# VG.net
KiCad netlist of a schematic drawn in Altium Designer
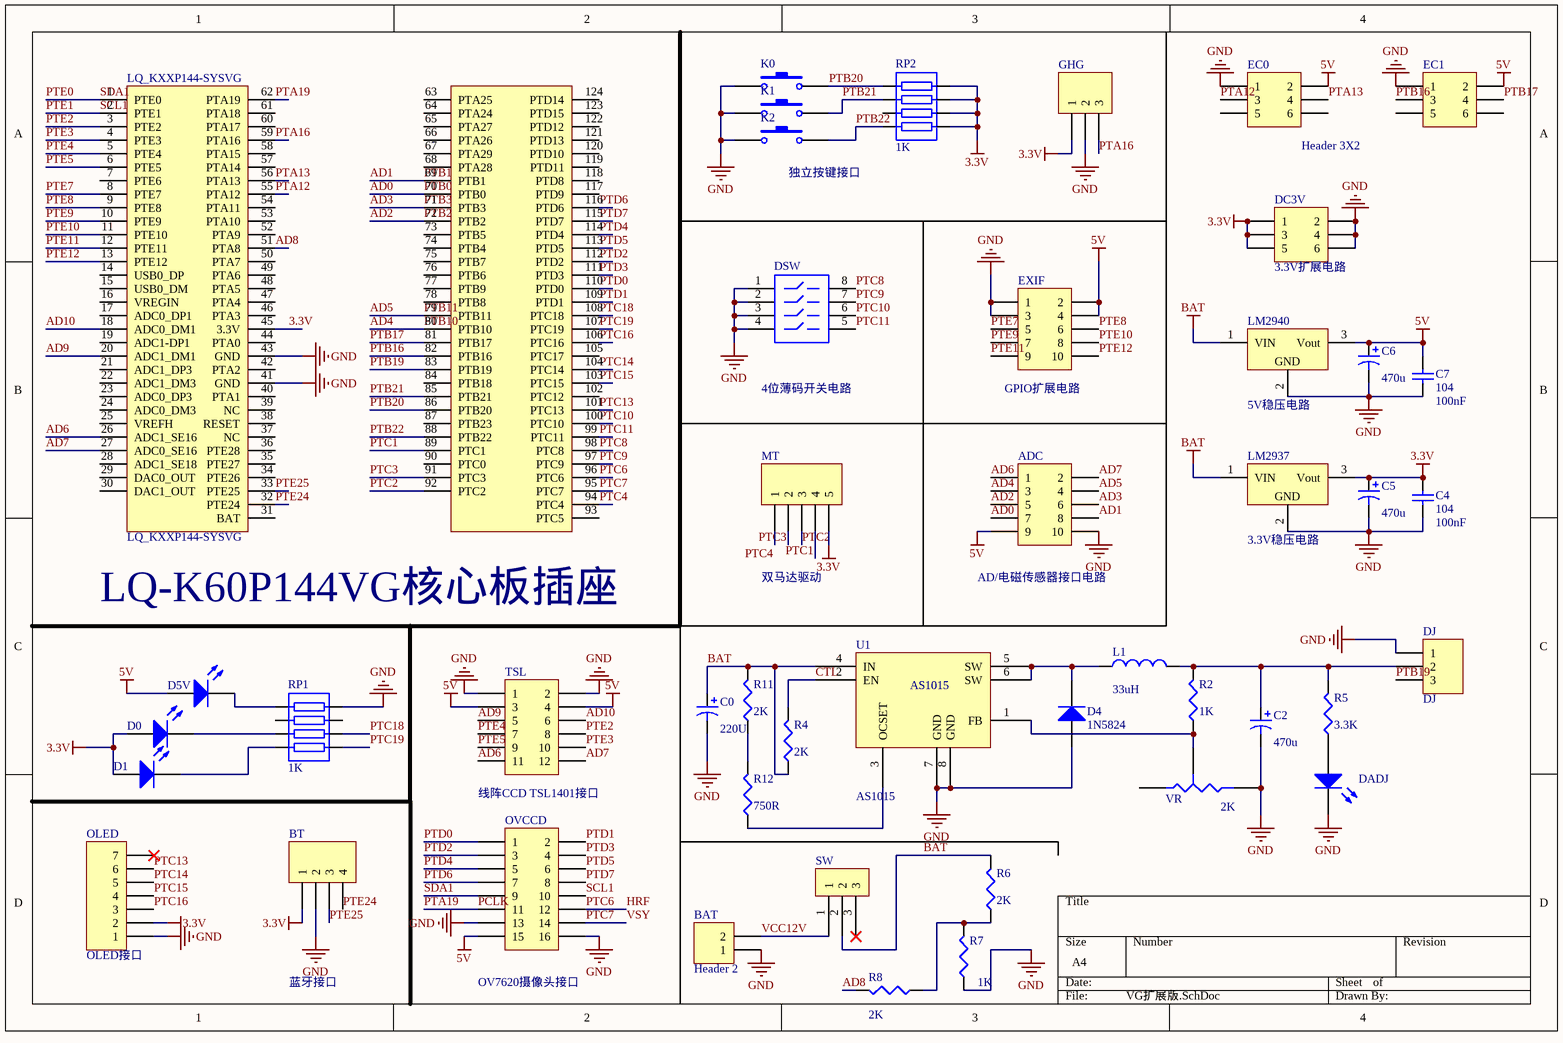
[diagram p0: VG扩展版.SchDoc]

(export (version "E")
  (design (tool "Eeschema 10.0.6"))
  (components
    (comp (ref "ADC")
      (value "AD/电磁传感器接口电路")
      (footprint "HDR2X5")
      (description "Header, 5-Pin, Dual row")
      (fields (field (name "PUBLISHER") "Altium Limited"))
      (libsource (lib "VG扩展板") (part "Header 5X2"))
    )
    (comp (ref "BAT")
      (value "Header 2")
      (footprint "power1")
      (description "Header, 2-Pin")
      (fields (field (name "PUBLISHER") "Altium Limited"))
      (libsource (lib "VG扩展板") (part "Header 2"))
    )
    (comp (ref "BT")
      (value "蓝牙接口")
      (footprint "HDR1X4")
      (description "Header, 4-Pin")
      (fields (field (name "PUBLISHER") "Altium Limited"))
      (libsource (lib "VG扩展板") (part "Header 4"))
    )
    (comp (ref "C0")
      (value "220U")
      (footprint "rb -5")
      (description "Polarized Capacitor (Radial)")
      (fields (field (name "PUBLISHER") "Altium Limited"))
      (libsource (lib "VG扩展板") (part "Cap Pol1"))
    )
    (comp (ref "C2")
      (value "470u")
      (footprint "3527")
      (description "Polarized Capacitor (Surface Mount)")
      (fields (field (name "PUBLISHER") "Altium Limited"))
      (libsource (lib "VG扩展板") (part "Cap Pol3"))
    )
    (comp (ref "C4")
      (value "104")
      (footprint "0603")
      (description "Capacitor (Semiconductor SIM Model)")
      (fields (field (name "ALTIUM_VALUE") "100nF") (field (name "PUBLISHER") "Altium Limited"))
      (libsource (lib "VG扩展板") (part "Cap Semi"))
    )
    (comp (ref "C5")
      (value "470u")
      (footprint "3527")
      (description "Polarized Capacitor (Surface Mount)")
      (fields (field (name "PUBLISHER") "Altium Limited"))
      (libsource (lib "VG扩展板") (part "Cap Pol3"))
    )
    (comp (ref "C6")
      (value "470u")
      (footprint "3527")
      (description "Polarized Capacitor (Surface Mount)")
      (fields (field (name "PUBLISHER") "Altium Limited"))
      (libsource (lib "VG扩展板") (part "Cap Pol3"))
    )
    (comp (ref "C7")
      (value "104")
      (footprint "0603")
      (description "Capacitor (Semiconductor SIM Model)")
      (fields (field (name "ALTIUM_VALUE") "100nF") (field (name "PUBLISHER") "Altium Limited"))
      (libsource (lib "VG扩展板") (part "Cap Semi"))
    )
    (comp (ref "D0")
      (value "~")
      (footprint "3.2X1.6X1.1")
      (description "Typical BLUE SiC LED")
      (fields (field (name "PUBLISHER") "Altium Limited"))
      (libsource (lib "VG扩展板") (part "LED3"))
    )
    (comp (ref "D1")
      (value "~")
      (footprint "3.2X1.6X1.1")
      (description "Typical BLUE SiC LED")
      (fields (field (name "PUBLISHER") "Altium Limited"))
      (libsource (lib "VG扩展板") (part "LED3"))
    )
    (comp (ref "D4")
      (value "1N5824")
      (footprint "1812_DIODE")
      (description "Default Diode")
      (fields (field (name "PUBLISHER") "Altium Limited"))
      (libsource (lib "VG扩展板") (part "Diode"))
    )
    (comp (ref "D5V")
      (value "~")
      (footprint "3.2X1.6X1.1")
      (description "Typical BLUE SiC LED")
      (fields (field (name "PUBLISHER") "Altium Limited"))
      (libsource (lib "VG扩展板") (part "LED3"))
    )
    (comp (ref "DADJ")
      (value "~")
      (footprint "3.2X1.6X1.1")
      (description "Typical BLUE SiC LED")
      (fields (field (name "PUBLISHER") "Altium Limited"))
      (libsource (lib "VG扩展板") (part "LED3"))
    )
    (comp (ref "DC3V")
      (value "3.3V扩展电路")
      (footprint "HDR2X3")
      (description "Header, 3-Pin, Dual row, Right Angle")
      (fields (field (name "PUBLISHER") "Altium Limited"))
      (libsource (lib "VG扩展板") (part "Header 3X2H"))
    )
    (comp (ref "DJ")
      (value "DJ")
      (footprint "HDR1X3")
      (description "Header, 3-Pin")
      (fields (field (name "PUBLISHER") "Altium Limited"))
      (libsource (lib "VG扩展板") (part "Header 3"))
    )
    (comp (ref "DSW")
      (value "4位薄码开关电路")
      (footprint "DIP-8")
      (description "DIP Switch")
      (fields (field (name "PUBLISHER") "Altium Limited"))
      (libsource (lib "VG扩展板") (part "SW-DIP4"))
    )
    (comp (ref "EC0")
      (value "~")
      (footprint "HDR2X3")
      (description "Header, 3-Pin, Dual row")
      (fields (field (name "PUBLISHER") "Altium Limited"))
      (libsource (lib "VG扩展板") (part "Header 3X2"))
    )
    (comp (ref "EC1")
      (value "Header 3X2")
      (footprint "HDR2X3")
      (description "Header, 3-Pin, Dual row")
      (fields (field (name "PUBLISHER") "Altium Limited"))
      (libsource (lib "VG扩展板") (part "Header 3X2"))
    )
    (comp (ref "EXIF")
      (value "GPIO扩展电路")
      (footprint "HDR2X5")
      (description "Header, 5-Pin, Dual row")
      (fields (field (name "PUBLISHER") "Altium Limited"))
      (libsource (lib "VG扩展板") (part "Header 5X2"))
    )
    (comp (ref "GHG")
      (value "~")
      (footprint "HDR1X3")
      (description "Header, 3-Pin")
      (fields (field (name "PUBLISHER") "Altium Limited"))
      (libsource (lib "") (part "Header 3_1"))
    )
    (comp (ref "K0")
      (value "~")
      (footprint "2512R")
      (description "Switch")
      (fields (field (name "PUBLISHER") "Altium Limited"))
      (libsource (lib "VG扩展板") (part "SW-PB"))
    )
    (comp (ref "K1")
      (value "~")
      (footprint "2512R")
      (description "Switch")
      (fields (field (name "PUBLISHER") "Altium Limited"))
      (libsource (lib "VG扩展板") (part "SW-PB"))
    )
    (comp (ref "K2")
      (value "~")
      (footprint "2512R")
      (description "Switch")
      (fields (field (name "PUBLISHER") "Altium Limited"))
      (libsource (lib "VG扩展板") (part "SW-PB"))
    )
    (comp (ref "L1")
      (value "33uH")
      (footprint "CL1010")
      (description "Inductor")
      (fields (field (name "PUBLISHER") "Altium Limited"))
      (libsource (lib "VG扩展板") (part "Inductor"))
    )
    (comp (ref "LM2937")
      (value "3.3V稳压电路")
      (footprint "TO263-3")
      (description "固定5V输出直流稳压芯片")
      (libsource (lib "VG扩展板") (part "LM2940"))
    )
    (comp (ref "LM2940")
      (value "5V稳压电路")
      (footprint "TO263-3")
      (description "固定5V输出直流稳压芯片")
      (libsource (lib "VG扩展板") (part "LM2940"))
    )
    (comp (ref "LQ_KXXP144-SYSVG")
      (value "LQ_KXXP144-SYSVG")
      (footprint "LQ_KXXP144-SYSVG")
      (libsource (lib "VG扩展板") (part "LQ_KXXP144-SYSVG"))
    )
    (comp (ref "MT")
      (value "双马达驱动")
      (footprint "HDR1X5")
      (description "Header, 5-Pin")
      (fields (field (name "PUBLISHER") "Altium Limited"))
      (libsource (lib "VG扩展板") (part "Header 5"))
    )
    (comp (ref "OLED")
      (value "OLED接口")
      (footprint "HDR1X7")
      (description "Header, 7-Pin")
      (fields (field (name "PUBLISHER") "Altium Limited"))
      (libsource (lib "VG扩展板") (part "Header 7"))
    )
    (comp (ref "OVCCD")
      (value "OV7620摄像头接口")
      (footprint "HDR2X8")
      (description "Header, 8-Pin, Dual row")
      (fields (field (name "PUBLISHER") "Altium Limited"))
      (libsource (lib "VG扩展板") (part "Header 8X2"))
    )
    (comp (ref "R2")
      (value "1K")
      (footprint "J1-0603")
      (description "Resistor")
      (fields (field (name "PUBLISHER") "Altium Limited"))
      (libsource (lib "VG扩展板") (part "Res3"))
    )
    (comp (ref "R4")
      (value "2K")
      (footprint "J1-0603")
      (description "Resistor")
      (fields (field (name "PUBLISHER") "Altium Limited"))
      (libsource (lib "VG扩展板") (part "Res3"))
    )
    (comp (ref "R5")
      (value "3.3K")
      (footprint "J1-0603")
      (description "Resistor")
      (fields (field (name "PUBLISHER") "Altium Limited"))
      (libsource (lib "VG扩展板") (part "Res3"))
    )
    (comp (ref "R6")
      (value "2K")
      (footprint "J1-0603")
      (description "Resistor")
      (fields (field (name "PUBLISHER") "Altium Limited"))
      (libsource (lib "VG扩展板") (part "Res3"))
    )
    (comp (ref "R7")
      (value "1K")
      (footprint "J1-0603")
      (description "Resistor")
      (fields (field (name "PUBLISHER") "Altium Limited"))
      (libsource (lib "VG扩展板") (part "Res3"))
    )
    (comp (ref "R8")
      (value "2K")
      (footprint "J1-0603")
      (description "Resistor")
      (fields (field (name "PUBLISHER") "Altium Limited"))
      (libsource (lib "VG扩展板") (part "Res3"))
    )
    (comp (ref "R11")
      (value "2K")
      (footprint "J1-0603")
      (description "Resistor")
      (fields (field (name "PUBLISHER") "Altium Limited"))
      (libsource (lib "VG扩展板") (part "Res3"))
    )
    (comp (ref "R12")
      (value "750R")
      (footprint "J1-0603")
      (description "Resistor")
      (fields (field (name "PUBLISHER") "Altium Limited"))
      (libsource (lib "VG扩展板") (part "Res3"))
    )
    (comp (ref "RP1") (value "1K") (footprint "RESPACK4_SMD") (libsource (lib "VG扩展板") (part "RESPACK4")))
    (comp (ref "RP2") (value "1K") (footprint "RESPACK4_SMD") (libsource (lib "VG扩展板") (part "RESPACK4")))
    (comp (ref "SW") (value "~") (footprint "钮子开关 - duplicate") (libsource (lib "VG扩展板") (part "钮子开关")))
    (comp (ref "TSL")
      (value "线阵CCD TSL1401接口")
      (footprint "HDR2X6")
      (description "Header, 6-Pin, Dual row")
      (fields (field (name "PUBLISHER") "Altium Limited"))
      (libsource (lib "VG扩展板") (part "Header 6X2"))
    )
    (comp (ref "U1") (value "AS1015") (footprint "SOP8L") (libsource (lib "VG扩展板") (part "AS1015")))
    (comp (ref "VR")
      (value "2K")
      (footprint "3362")
      (description "Tapped Resistor")
      (fields (field (name "PUBLISHER") "Altium Limited"))
      (libsource (lib "VG扩展板") (part "Res Tap"))
    )
  )
  (nets
    (net (code "1") (name "/AD0") (class "Default")
      (node (ref "ADC") (pin "7") (pinfunction "7_7") (pintype "passive"))
      (node (ref "LQ_KXXP144-SYSVG") (pin "70") (pinfunction "PTB0_70") (pintype "passive"))
    )
    (net (code "2") (name "/AD1") (class "Default")
      (node (ref "ADC") (pin "8") (pinfunction "8_8") (pintype "passive"))
      (node (ref "LQ_KXXP144-SYSVG") (pin "69") (pinfunction "PTB1_69") (pintype "passive"))
    )
    (net (code "3") (name "/AD2") (class "Default")
      (node (ref "ADC") (pin "5") (pinfunction "5_5") (pintype "passive"))
      (node (ref "LQ_KXXP144-SYSVG") (pin "72") (pinfunction "PTB2_72") (pintype "passive"))
    )
    (net (code "4") (name "/AD3") (class "Default")
      (node (ref "ADC") (pin "6") (pinfunction "6_6") (pintype "passive"))
      (node (ref "LQ_KXXP144-SYSVG") (pin "71") (pinfunction "PTB3_71") (pintype "passive"))
    )
    (net (code "5") (name "/AD4") (class "Default")
      (node (ref "ADC") (pin "3") (pinfunction "3_3") (pintype "passive"))
      (node (ref "LQ_KXXP144-SYSVG") (pin "80") (pinfunction "PTB10_80") (pintype "passive"))
    )
    (net (code "6") (name "/AD5") (class "Default")
      (node (ref "ADC") (pin "4") (pinfunction "4_4") (pintype "passive"))
      (node (ref "LQ_KXXP144-SYSVG") (pin "79") (pinfunction "PTB11_79") (pintype "passive"))
    )
    (net (code "7") (name "/AD6") (class "Default")
      (node (ref "ADC") (pin "1") (pinfunction "1_1") (pintype "passive"))
      (node (ref "LQ_KXXP144-SYSVG") (pin "26") (pinfunction "ADC1_SE16_26") (pintype "passive"))
      (node (ref "TSL") (pin "11") (pinfunction "11_11") (pintype "passive"))
    )
    (net (code "8") (name "/AD7") (class "Default")
      (node (ref "ADC") (pin "2") (pinfunction "2_2") (pintype "passive"))
      (node (ref "LQ_KXXP144-SYSVG") (pin "27") (pinfunction "ADC0_SE16_27") (pintype "passive"))
      (node (ref "TSL") (pin "12") (pinfunction "12_12") (pintype "passive"))
    )
    (net (code "9") (name "/AD8") (class "Default")
      (node (ref "LQ_KXXP144-SYSVG") (pin "51") (pinfunction "PTA8_51") (pintype "passive"))
      (node (ref "R8") (pin "2") (pinfunction "2_2") (pintype "passive"))
    )
    (net (code "10") (name "/AD9") (class "Default")
      (node (ref "LQ_KXXP144-SYSVG") (pin "20") (pinfunction "ADC1_DM1_20") (pintype "passive"))
      (node (ref "TSL") (pin "5") (pinfunction "5_5") (pintype "passive"))
    )
    (net (code "11") (name "/AD10") (class "Default")
      (node (ref "LQ_KXXP144-SYSVG") (pin "18") (pinfunction "ADC0_DM1_18") (pintype "passive"))
      (node (ref "TSL") (pin "6") (pinfunction "6_6") (pintype "passive"))
    )
    (net (code "12") (name "/CTL") (class "Default")
      (node (ref "R4") (pin "2") (pinfunction "2_2") (pintype "passive"))
      (node (ref "U1") (pin "2") (pinfunction "EN_2") (pintype "passive"))
    )
    (net (code "13") (name "/HRF") (class "Default")
      (node (ref "LQ_KXXP144-SYSVG") (pin "96") (pinfunction "PTC6_96") (pintype "passive"))
      (node (ref "OVCCD") (pin "12") (pinfunction "12_12") (pintype "passive"))
    )
    (net (code "14") (name "/PCLK") (class "Default")
      (node (ref "LQ_KXXP144-SYSVG") (pin "62") (pinfunction "PTA19_62") (pintype "passive"))
      (node (ref "OVCCD") (pin "11") (pinfunction "11_11") (pintype "passive"))
    )
    (net (code "15") (name "/PTA12") (class "Default")
      (node (ref "EC0") (pin "3") (pinfunction "3_3") (pintype "passive"))
      (node (ref "LQ_KXXP144-SYSVG") (pin "55") (pinfunction "PTA12_55") (pintype "passive"))
    )
    (net (code "16") (name "/PTA13") (class "Default")
      (node (ref "EC0") (pin "4") (pinfunction "4_4") (pintype "passive"))
      (node (ref "LQ_KXXP144-SYSVG") (pin "56") (pinfunction "PTA13_56") (pintype "passive"))
    )
    (net (code "17") (name "/PTA16") (class "Default")
      (node (ref "GHG") (pin "3") (pinfunction "3_3") (pintype "passive"))
      (node (ref "LQ_KXXP144-SYSVG") (pin "59") (pinfunction "PTA16_59") (pintype "passive"))
    )
    (net (code "18") (name "/PTB16") (class "Default")
      (node (ref "EC1") (pin "3") (pinfunction "3_3") (pintype "passive"))
      (node (ref "LQ_KXXP144-SYSVG") (pin "82") (pinfunction "PTB16_82") (pintype "passive"))
    )
    (net (code "19") (name "/PTB17") (class "Default")
      (node (ref "EC1") (pin "4") (pinfunction "4_4") (pintype "passive"))
      (node (ref "LQ_KXXP144-SYSVG") (pin "81") (pinfunction "PTB17_81") (pintype "passive"))
    )
    (net (code "20") (name "/PTB19") (class "Default")
      (node (ref "DJ") (pin "3") (pinfunction "3_3") (pintype "passive"))
      (node (ref "LQ_KXXP144-SYSVG") (pin "83") (pinfunction "PTB19_83") (pintype "passive"))
    )
    (net (code "21") (name "/PTB20") (class "Default")
      (node (ref "K0") (pin "2") (pinfunction "2_2") (pintype "passive"))
      (node (ref "LQ_KXXP144-SYSVG") (pin "86") (pinfunction "PTB20_86") (pintype "passive"))
      (node (ref "RP2") (pin "1") (pinfunction "1_1") (pintype "passive"))
    )
    (net (code "22") (name "/PTB21") (class "Default")
      (node (ref "K1") (pin "2") (pinfunction "2_2") (pintype "passive"))
      (node (ref "LQ_KXXP144-SYSVG") (pin "85") (pinfunction "PTB21_85") (pintype "passive"))
      (node (ref "RP2") (pin "3") (pinfunction "3_3") (pintype "passive"))
    )
    (net (code "23") (name "/PTB22") (class "Default")
      (node (ref "K2") (pin "2") (pinfunction "2_2") (pintype "passive"))
      (node (ref "LQ_KXXP144-SYSVG") (pin "88") (pinfunction "PTB22_88") (pintype "passive"))
      (node (ref "RP2") (pin "7") (pinfunction "7_7") (pintype "passive"))
    )
    (net (code "24") (name "/PTC1") (class "Default")
      (node (ref "LQ_KXXP144-SYSVG") (pin "89") (pinfunction "PTC1_89") (pintype "passive"))
      (node (ref "MT") (pin "4") (pinfunction "4_4") (pintype "passive"))
    )
    (net (code "25") (name "/PTC2") (class "Default")
      (node (ref "LQ_KXXP144-SYSVG") (pin "92") (pinfunction "PTC2_92") (pintype "passive"))
      (node (ref "MT") (pin "3") (pinfunction "3_3") (pintype "passive"))
    )
    (net (code "26") (name "/PTC3") (class "Default")
      (node (ref "LQ_KXXP144-SYSVG") (pin "91") (pinfunction "PTC3_91") (pintype "passive"))
      (node (ref "MT") (pin "2") (pinfunction "2_2") (pintype "passive"))
    )
    (net (code "27") (name "/PTC4") (class "Default")
      (node (ref "LQ_KXXP144-SYSVG") (pin "94") (pinfunction "PTC4_94") (pintype "passive"))
      (node (ref "MT") (pin "1") (pinfunction "1_1") (pintype "passive"))
    )
    (net (code "28") (name "/PTC7") (class "Default")
      (node (ref "LQ_KXXP144-SYSVG") (pin "95") (pinfunction "PTC7_95") (pintype "passive"))
      (node (ref "OVCCD") (pin "14") (pinfunction "14_14") (pintype "passive"))
    )
    (net (code "29") (name "/PTC8") (class "Default")
      (node (ref "DSW") (pin "8") (pinfunction "8_8") (pintype "passive"))
      (node (ref "LQ_KXXP144-SYSVG") (pin "98") (pinfunction "PTC8_98") (pintype "passive"))
    )
    (net (code "30") (name "/PTC9") (class "Default")
      (node (ref "DSW") (pin "7") (pinfunction "7_7") (pintype "passive"))
      (node (ref "LQ_KXXP144-SYSVG") (pin "97") (pinfunction "PTC9_97") (pintype "passive"))
    )
    (net (code "31") (name "/PTC10") (class "Default")
      (node (ref "DSW") (pin "6") (pinfunction "6_6") (pintype "passive"))
      (node (ref "LQ_KXXP144-SYSVG") (pin "100") (pinfunction "PTC10_100") (pintype "passive"))
    )
    (net (code "32") (name "/PTC11") (class "Default")
      (node (ref "DSW") (pin "5") (pinfunction "5_5") (pintype "passive"))
      (node (ref "LQ_KXXP144-SYSVG") (pin "99") (pinfunction "PTC11_99") (pintype "passive"))
    )
    (net (code "33") (name "/PTC13") (class "Default")
      (node (ref "LQ_KXXP144-SYSVG") (pin "101") (pinfunction "PTC13_101") (pintype "passive"))
      (node (ref "OLED") (pin "6") (pinfunction "6_6") (pintype "passive"))
    )
    (net (code "34") (name "/PTC14") (class "Default")
      (node (ref "LQ_KXXP144-SYSVG") (pin "104") (pinfunction "PTC14_104") (pintype "passive"))
      (node (ref "OLED") (pin "5") (pinfunction "5_5") (pintype "passive"))
    )
    (net (code "35") (name "/PTC15") (class "Default")
      (node (ref "LQ_KXXP144-SYSVG") (pin "103") (pinfunction "PTC15_103") (pintype "passive"))
      (node (ref "OLED") (pin "4") (pinfunction "4_4") (pintype "passive"))
    )
    (net (code "36") (name "/PTC16") (class "Default")
      (node (ref "LQ_KXXP144-SYSVG") (pin "106") (pinfunction "PTC16_106") (pintype "passive"))
      (node (ref "OLED") (pin "3") (pinfunction "3_3") (pintype "passive"))
    )
    (net (code "37") (name "/PTC18") (class "Default")
      (node (ref "LQ_KXXP144-SYSVG") (pin "108") (pinfunction "PTC18_108") (pintype "passive"))
      (node (ref "RP1") (pin "6") (pinfunction "6_6") (pintype "passive"))
    )
    (net (code "38") (name "/PTC19") (class "Default")
      (node (ref "LQ_KXXP144-SYSVG") (pin "107") (pinfunction "PTC19_107") (pintype "passive"))
      (node (ref "RP1") (pin "8") (pinfunction "8_8") (pintype "passive"))
    )
    (net (code "39") (name "/PTD0") (class "Default")
      (node (ref "LQ_KXXP144-SYSVG") (pin "110") (pinfunction "PTD0_110") (pintype "passive"))
      (node (ref "OVCCD") (pin "1") (pinfunction "1_1") (pintype "passive"))
    )
    (net (code "40") (name "/PTD1") (class "Default")
      (node (ref "LQ_KXXP144-SYSVG") (pin "109") (pinfunction "PTD1_109") (pintype "passive"))
      (node (ref "OVCCD") (pin "2") (pinfunction "2_2") (pintype "passive"))
    )
    (net (code "41") (name "/PTD2") (class "Default")
      (node (ref "LQ_KXXP144-SYSVG") (pin "112") (pinfunction "PTD2_112") (pintype "passive"))
      (node (ref "OVCCD") (pin "3") (pinfunction "3_3") (pintype "passive"))
    )
    (net (code "42") (name "/PTD3") (class "Default")
      (node (ref "LQ_KXXP144-SYSVG") (pin "111") (pinfunction "PTD3_111") (pintype "passive"))
      (node (ref "OVCCD") (pin "4") (pinfunction "4_4") (pintype "passive"))
    )
    (net (code "43") (name "/PTD4") (class "Default")
      (node (ref "LQ_KXXP144-SYSVG") (pin "114") (pinfunction "PTD4_114") (pintype "passive"))
      (node (ref "OVCCD") (pin "5") (pinfunction "5_5") (pintype "passive"))
    )
    (net (code "44") (name "/PTD5") (class "Default")
      (node (ref "LQ_KXXP144-SYSVG") (pin "113") (pinfunction "PTD5_113") (pintype "passive"))
      (node (ref "OVCCD") (pin "6") (pinfunction "6_6") (pintype "passive"))
    )
    (net (code "45") (name "/PTD6") (class "Default")
      (node (ref "LQ_KXXP144-SYSVG") (pin "116") (pinfunction "PTD6_116") (pintype "passive"))
      (node (ref "OVCCD") (pin "7") (pinfunction "7_7") (pintype "passive"))
    )
    (net (code "46") (name "/PTD7") (class "Default")
      (node (ref "LQ_KXXP144-SYSVG") (pin "115") (pinfunction "PTD7_115") (pintype "passive"))
      (node (ref "OVCCD") (pin "8") (pinfunction "8_8") (pintype "passive"))
    )
    (net (code "47") (name "/PTE0") (class "Default")
      (node (ref "LQ_KXXP144-SYSVG") (pin "1") (pinfunction "PTE0_1") (pintype "passive"))
      (node (ref "OVCCD") (pin "9") (pinfunction "9_9") (pintype "passive"))
    )
    (net (code "48") (name "/PTE1") (class "Default")
      (node (ref "LQ_KXXP144-SYSVG") (pin "2") (pinfunction "PTE1_2") (pintype "passive"))
      (node (ref "OVCCD") (pin "10") (pinfunction "10_10") (pintype "passive"))
    )
    (net (code "49") (name "/PTE2") (class "Default")
      (node (ref "LQ_KXXP144-SYSVG") (pin "3") (pinfunction "PTE2_3") (pintype "passive"))
      (node (ref "TSL") (pin "8") (pinfunction "8_8") (pintype "passive"))
    )
    (net (code "50") (name "/PTE3") (class "Default")
      (node (ref "LQ_KXXP144-SYSVG") (pin "4") (pinfunction "PTE3_4") (pintype "passive"))
      (node (ref "TSL") (pin "10") (pinfunction "10_10") (pintype "passive"))
    )
    (net (code "51") (name "/PTE4") (class "Default")
      (node (ref "LQ_KXXP144-SYSVG") (pin "5") (pinfunction "PTE4_5") (pintype "passive"))
      (node (ref "TSL") (pin "7") (pinfunction "7_7") (pintype "passive"))
    )
    (net (code "52") (name "/PTE5") (class "Default")
      (node (ref "LQ_KXXP144-SYSVG") (pin "6") (pinfunction "PTE5_6") (pintype "passive"))
      (node (ref "TSL") (pin "9") (pinfunction "9_9") (pintype "passive"))
    )
    (net (code "53") (name "/PTE7") (class "Default")
      (node (ref "EXIF") (pin "5") (pinfunction "5_5") (pintype "passive"))
      (node (ref "LQ_KXXP144-SYSVG") (pin "8") (pinfunction "PTE7_8") (pintype "passive"))
    )
    (net (code "54") (name "/PTE8") (class "Default")
      (node (ref "EXIF") (pin "6") (pinfunction "6_6") (pintype "passive"))
      (node (ref "LQ_KXXP144-SYSVG") (pin "9") (pinfunction "PTE8_9") (pintype "passive"))
    )
    (net (code "55") (name "/PTE9") (class "Default")
      (node (ref "EXIF") (pin "7") (pinfunction "7_7") (pintype "passive"))
      (node (ref "LQ_KXXP144-SYSVG") (pin "10") (pinfunction "PTE9_10") (pintype "passive"))
    )
    (net (code "56") (name "/PTE10") (class "Default")
      (node (ref "EXIF") (pin "8") (pinfunction "8_8") (pintype "passive"))
      (node (ref "LQ_KXXP144-SYSVG") (pin "11") (pinfunction "PTE10_11") (pintype "passive"))
    )
    (net (code "57") (name "/PTE11") (class "Default")
      (node (ref "EXIF") (pin "9") (pinfunction "9_9") (pintype "passive"))
      (node (ref "LQ_KXXP144-SYSVG") (pin "12") (pinfunction "PTE11_12") (pintype "passive"))
    )
    (net (code "58") (name "/PTE12") (class "Default")
      (node (ref "EXIF") (pin "10") (pinfunction "10_10") (pintype "passive"))
      (node (ref "LQ_KXXP144-SYSVG") (pin "13") (pinfunction "PTE12_13") (pintype "passive"))
    )
    (net (code "59") (name "/PTE24") (class "Default")
      (node (ref "BT") (pin "4") (pinfunction "4_4") (pintype "passive"))
      (node (ref "LQ_KXXP144-SYSVG") (pin "32") (pinfunction "PTE24_32") (pintype "passive"))
    )
    (net (code "60") (name "/PTE25") (class "Default")
      (node (ref "BT") (pin "3") (pinfunction "3_3") (pintype "passive"))
      (node (ref "LQ_KXXP144-SYSVG") (pin "33") (pinfunction "PTE25_33") (pintype "passive"))
    )
    (net (code "61") (name "/VCC12V") (class "Default")
      (node (ref "BAT") (pin "2") (pinfunction "2_2") (pintype "passive"))
      (node (ref "SW") (pin "1") (pinfunction "1_1") (pintype "passive"))
    )
    (net (code "62") (name "3.3V") (class "Default")
      (node (ref "BT") (pin "1") (pinfunction "1_1") (pintype "passive"))
      (node (ref "C4") (pin "2") (pinfunction "2_2") (pintype "passive"))
      (node (ref "C5") (pin "1") (pinfunction "1_1") (pintype "passive"))
      (node (ref "D0") (pin "1") (pinfunction "A_1") (pintype "passive"))
      (node (ref "D1") (pin "1") (pinfunction "A_1") (pintype "passive"))
      (node (ref "DC3V") (pin "1") (pinfunction "1_1") (pintype "passive"))
      (node (ref "DC3V") (pin "3") (pinfunction "3_3") (pintype "passive"))
      (node (ref "DC3V") (pin "5") (pinfunction "5_5") (pintype "passive"))
      (node (ref "GHG") (pin "1") (pinfunction "1_1") (pintype "passive"))
      (node (ref "LM2937") (pin "3") (pinfunction "Vout_3") (pintype "passive"))
      (node (ref "LQ_KXXP144-SYSVG") (pin "45") (pinfunction "3.3V_45") (pintype "passive"))
      (node (ref "MT") (pin "5") (pinfunction "5_5") (pintype "passive"))
      (node (ref "OLED") (pin "2") (pinfunction "2_2") (pintype "passive"))
      (node (ref "RP2") (pin "2") (pinfunction "2_2") (pintype "passive"))
      (node (ref "RP2") (pin "4") (pinfunction "4_4") (pintype "passive"))
      (node (ref "RP2") (pin "6") (pinfunction "6_6") (pintype "passive"))
      (node (ref "RP2") (pin "8") (pinfunction "8_8") (pintype "passive"))
    )
    (net (code "63") (name "5V") (class "Default")
      (node (ref "ADC") (pin "9") (pinfunction "9_9") (pintype "passive"))
      (node (ref "C6") (pin "1") (pinfunction "1_1") (pintype "passive"))
      (node (ref "C7") (pin "2") (pinfunction "2_2") (pintype "passive"))
      (node (ref "D5V") (pin "1") (pinfunction "A_1") (pintype "passive"))
      (node (ref "EC0") (pin "2") (pinfunction "2_2") (pintype "passive"))
      (node (ref "EC1") (pin "2") (pinfunction "2_2") (pintype "passive"))
      (node (ref "EXIF") (pin "2") (pinfunction "2_2") (pintype "passive"))
      (node (ref "EXIF") (pin "4") (pinfunction "4_4") (pintype "passive"))
      (node (ref "LM2940") (pin "3") (pinfunction "Vout_3") (pintype "passive"))
      (node (ref "OVCCD") (pin "15") (pinfunction "15_15") (pintype "passive"))
      (node (ref "TSL") (pin "3") (pinfunction "3_3") (pintype "passive"))
      (node (ref "TSL") (pin "4") (pinfunction "4_4") (pintype "passive"))
    )
    (net (code "64") (name "BAT") (class "Default")
      (node (ref "C0") (pin "1") (pinfunction "1_1") (pintype "passive"))
      (node (ref "LM2937") (pin "1") (pinfunction "VIN_1") (pintype "passive"))
      (node (ref "LM2940") (pin "1") (pinfunction "VIN_1") (pintype "passive"))
      (node (ref "R11") (pin "2") (pinfunction "2_2") (pintype "passive"))
      (node (ref "R4") (pin "1") (pinfunction "1_1") (pintype "passive"))
      (node (ref "R6") (pin "2") (pinfunction "2_2") (pintype "passive"))
      (node (ref "SW") (pin "2") (pinfunction "2_2") (pintype "passive"))
      (node (ref "U1") (pin "4") (pinfunction "IN_4") (pintype "passive"))
    )
    (net (code "65") (name "GND") (class "Default")
      (node (ref "ADC") (pin "10") (pinfunction "10_10") (pintype "passive"))
      (node (ref "BAT") (pin "1") (pinfunction "1_1") (pintype "passive"))
      (node (ref "BT") (pin "2") (pinfunction "2_2") (pintype "passive"))
      (node (ref "C0") (pin "2") (pinfunction "2_2") (pintype "passive"))
      (node (ref "C2") (pin "2") (pinfunction "2_2") (pintype "passive"))
      (node (ref "C4") (pin "1") (pinfunction "1_1") (pintype "passive"))
      (node (ref "C5") (pin "2") (pinfunction "2_2") (pintype "passive"))
      (node (ref "C6") (pin "2") (pinfunction "2_2") (pintype "passive"))
      (node (ref "C7") (pin "1") (pinfunction "1_1") (pintype "passive"))
      (node (ref "D4") (pin "1") (pinfunction "A_1") (pintype "passive"))
      (node (ref "DADJ") (pin "2") (pinfunction "K_2") (pintype "passive"))
      (node (ref "DC3V") (pin "2") (pinfunction "2_2") (pintype "passive"))
      (node (ref "DC3V") (pin "4") (pinfunction "4_4") (pintype "passive"))
      (node (ref "DC3V") (pin "6") (pinfunction "6_6") (pintype "passive"))
      (node (ref "DJ") (pin "1") (pinfunction "1_1") (pintype "passive"))
      (node (ref "DSW") (pin "1") (pinfunction "1_1") (pintype "passive"))
      (node (ref "DSW") (pin "2") (pinfunction "2_2") (pintype "passive"))
      (node (ref "DSW") (pin "3") (pinfunction "3_3") (pintype "passive"))
      (node (ref "DSW") (pin "4") (pinfunction "4_4") (pintype "passive"))
      (node (ref "EC0") (pin "1") (pinfunction "1_1") (pintype "passive"))
      (node (ref "EC1") (pin "1") (pinfunction "1_1") (pintype "passive"))
      (node (ref "EXIF") (pin "1") (pinfunction "1_1") (pintype "passive"))
      (node (ref "EXIF") (pin "3") (pinfunction "3_3") (pintype "passive"))
      (node (ref "GHG") (pin "2") (pinfunction "2_2") (pintype "passive"))
      (node (ref "K0") (pin "1") (pinfunction "1_1") (pintype "passive"))
      (node (ref "K1") (pin "1") (pinfunction "1_1") (pintype "passive"))
      (node (ref "K2") (pin "1") (pinfunction "1_1") (pintype "passive"))
      (node (ref "LM2937") (pin "2") (pinfunction "GND_2") (pintype "passive"))
      (node (ref "LM2940") (pin "2") (pinfunction "GND_2") (pintype "passive"))
      (node (ref "LQ_KXXP144-SYSVG") (pin "41") (pinfunction "GND_41") (pintype "passive"))
      (node (ref "LQ_KXXP144-SYSVG") (pin "43") (pinfunction "GND_43") (pintype "passive"))
      (node (ref "OLED") (pin "1") (pinfunction "1_1") (pintype "passive"))
      (node (ref "OVCCD") (pin "13") (pinfunction "13_13") (pintype "passive"))
      (node (ref "OVCCD") (pin "16") (pinfunction "16_16") (pintype "passive"))
      (node (ref "R7") (pin "1") (pinfunction "1_1") (pintype "passive"))
      (node (ref "RP1") (pin "2") (pinfunction "2_2") (pintype "passive"))
      (node (ref "TSL") (pin "1") (pinfunction "1_1") (pintype "passive"))
      (node (ref "TSL") (pin "2") (pinfunction "2_2") (pintype "passive"))
      (node (ref "U1") (pin "7") (pinfunction "GND_7") (pintype "passive"))
      (node (ref "U1") (pin "8") (pinfunction "GND_8") (pintype "passive"))
      (node (ref "VR") (pin "2") (pinfunction "B_2") (pintype "passive"))
    )
    (net (code "66") (name "Net-(C2-Pad1)") (class "Default")
      (node (ref "C2") (pin "1") (pinfunction "1_1") (pintype "passive"))
      (node (ref "DJ") (pin "2") (pinfunction "2_2") (pintype "passive"))
      (node (ref "L1") (pin "2") (pinfunction "2_2") (pintype "passive"))
      (node (ref "R2") (pin "2") (pinfunction "2_2") (pintype "passive"))
      (node (ref "R5") (pin "2") (pinfunction "2_2") (pintype "passive"))
    )
    (net (code "67") (name "Net-(D0-K)") (class "Default")
      (node (ref "D0") (pin "2") (pinfunction "K_2") (pintype "passive"))
      (node (ref "RP1") (pin "5") (pinfunction "5_5") (pintype "passive"))
    )
    (net (code "68") (name "Net-(D1-K)") (class "Default")
      (node (ref "D1") (pin "2") (pinfunction "K_2") (pintype "passive"))
      (node (ref "RP1") (pin "7") (pinfunction "7_7") (pintype "passive"))
    )
    (net (code "69") (name "Net-(D4-K)") (class "Default")
      (node (ref "D4") (pin "2") (pinfunction "K_2") (pintype "passive"))
      (node (ref "L1") (pin "1") (pinfunction "1_1") (pintype "passive"))
      (node (ref "U1") (pin "5") (pinfunction "SW_5") (pintype "passive"))
      (node (ref "U1") (pin "6") (pinfunction "SW_6") (pintype "passive"))
    )
    (net (code "70") (name "Net-(D5V-K)") (class "Default")
      (node (ref "D5V") (pin "2") (pinfunction "K_2") (pintype "passive"))
      (node (ref "RP1") (pin "1") (pinfunction "1_1") (pintype "passive"))
    )
    (net (code "71") (name "Net-(DADJ-A)") (class "Default")
      (node (ref "DADJ") (pin "1") (pinfunction "A_1") (pintype "passive"))
      (node (ref "R5") (pin "1") (pinfunction "1_1") (pintype "passive"))
    )
    (net (code "72") (name "Net-(R6-Pad1)") (class "Default")
      (node (ref "R6") (pin "1") (pinfunction "1_1") (pintype "passive"))
      (node (ref "R7") (pin "2") (pinfunction "2_2") (pintype "passive"))
      (node (ref "R8") (pin "1") (pinfunction "1_1") (pintype "passive"))
    )
    (net (code "73") (name "Net-(R11-Pad1)") (class "Default")
      (node (ref "R11") (pin "1") (pinfunction "1_1") (pintype "passive"))
      (node (ref "R12") (pin "2") (pinfunction "2_2") (pintype "passive"))
    )
    (net (code "74") (name "Net-(U1-FB)") (class "Default")
      (node (ref "R2") (pin "1") (pinfunction "1_1") (pintype "passive"))
      (node (ref "U1") (pin "1") (pinfunction "FB_1") (pintype "passive"))
      (node (ref "VR") (pin "3") (pinfunction "TAP_3") (pintype "passive"))
    )
    (net (code "75") (name "Net-(U1-OCSET)") (class "Default")
      (node (ref "R12") (pin "1") (pinfunction "1_1") (pintype "passive"))
      (node (ref "U1") (pin "3") (pinfunction "OCSET_3") (pintype "passive"))
    )
    (net (code "76") (name "unconnected-(EC0-Pad5)") (class "Default")
      (node (ref "EC0") (pin "5") (pinfunction "5_5") (pintype "passive"))
    )
    (net (code "77") (name "unconnected-(EC0-Pad6)") (class "Default")
      (node (ref "EC0") (pin "6") (pinfunction "6_6") (pintype "passive"))
    )
    (net (code "78") (name "unconnected-(EC1-Pad5)") (class "Default")
      (node (ref "EC1") (pin "5") (pinfunction "5_5") (pintype "passive"))
    )
    (net (code "79") (name "unconnected-(EC1-Pad6)") (class "Default")
      (node (ref "EC1") (pin "6") (pinfunction "6_6") (pintype "passive"))
    )
    (net (code "80") (name "unconnected-(LQ_KXXP144-SYSVG-ADC0_DM3-Pad24)") (class "Default")
      (node (ref "LQ_KXXP144-SYSVG") (pin "24") (pinfunction "ADC0_DM3_24") (pintype "passive"))
    )
    (net (code "81") (name "unconnected-(LQ_KXXP144-SYSVG-ADC0_DP1-Pad17)") (class "Default")
      (node (ref "LQ_KXXP144-SYSVG") (pin "17") (pinfunction "ADC0_DP1_17") (pintype "passive"))
    )
    (net (code "82") (name "unconnected-(LQ_KXXP144-SYSVG-ADC0_DP3-Pad23)") (class "Default")
      (node (ref "LQ_KXXP144-SYSVG") (pin "23") (pinfunction "ADC0_DP3_23") (pintype "passive"))
    )
    (net (code "83") (name "unconnected-(LQ_KXXP144-SYSVG-ADC1-DP1-Pad19)") (class "Default")
      (node (ref "LQ_KXXP144-SYSVG") (pin "19") (pinfunction "ADC1-DP1_19") (pintype "passive"))
    )
    (net (code "84") (name "unconnected-(LQ_KXXP144-SYSVG-ADC1_DM3-Pad22)") (class "Default")
      (node (ref "LQ_KXXP144-SYSVG") (pin "22") (pinfunction "ADC1_DM3_22") (pintype "passive"))
    )
    (net (code "85") (name "unconnected-(LQ_KXXP144-SYSVG-ADC1_DP3-Pad21)") (class "Default")
      (node (ref "LQ_KXXP144-SYSVG") (pin "21") (pinfunction "ADC1_DP3_21") (pintype "passive"))
    )
    (net (code "86") (name "unconnected-(LQ_KXXP144-SYSVG-ADC1_SE18-Pad28)") (class "Default")
      (node (ref "LQ_KXXP144-SYSVG") (pin "28") (pinfunction "ADC1_SE18_28") (pintype "passive"))
    )
    (net (code "87") (name "unconnected-(LQ_KXXP144-SYSVG-BAT-Pad31)") (class "Default")
      (node (ref "LQ_KXXP144-SYSVG") (pin "31") (pinfunction "BAT_31") (pintype "passive"))
    )
    (net (code "88") (name "unconnected-(LQ_KXXP144-SYSVG-DAC0_OUT-Pad29)") (class "Default")
      (node (ref "LQ_KXXP144-SYSVG") (pin "29") (pinfunction "DAC0_OUT_29") (pintype "passive"))
    )
    (net (code "89") (name "unconnected-(LQ_KXXP144-SYSVG-DAC1_OUT-Pad30)") (class "Default")
      (node (ref "LQ_KXXP144-SYSVG") (pin "30") (pinfunction "DAC1_OUT_30") (pintype "passive"))
    )
    (net (code "90") (name "unconnected-(LQ_KXXP144-SYSVG-NC-Pad37)") (class "Default")
      (node (ref "LQ_KXXP144-SYSVG") (pin "37") (pinfunction "NC_37") (pintype "passive"))
    )
    (net (code "91") (name "unconnected-(LQ_KXXP144-SYSVG-NC-Pad39)") (class "Default")
      (node (ref "LQ_KXXP144-SYSVG") (pin "39") (pinfunction "NC_39") (pintype "passive"))
    )
    (net (code "92") (name "unconnected-(LQ_KXXP144-SYSVG-PTA0-Pad44)") (class "Default")
      (node (ref "LQ_KXXP144-SYSVG") (pin "44") (pinfunction "PTA0_44") (pintype "passive"))
    )
    (net (code "93") (name "unconnected-(LQ_KXXP144-SYSVG-PTA1-Pad40)") (class "Default")
      (node (ref "LQ_KXXP144-SYSVG") (pin "40") (pinfunction "PTA1_40") (pintype "passive"))
    )
    (net (code "94") (name "unconnected-(LQ_KXXP144-SYSVG-PTA2-Pad42)") (class "Default")
      (node (ref "LQ_KXXP144-SYSVG") (pin "42") (pinfunction "PTA2_42") (pintype "passive"))
    )
    (net (code "95") (name "unconnected-(LQ_KXXP144-SYSVG-PTA3-Pad46)") (class "Default")
      (node (ref "LQ_KXXP144-SYSVG") (pin "46") (pinfunction "PTA3_46") (pintype "passive"))
    )
    (net (code "96") (name "unconnected-(LQ_KXXP144-SYSVG-PTA4-Pad47)") (class "Default")
      (node (ref "LQ_KXXP144-SYSVG") (pin "47") (pinfunction "PTA4_47") (pintype "passive"))
    )
    (net (code "97") (name "unconnected-(LQ_KXXP144-SYSVG-PTA5-Pad48)") (class "Default")
      (node (ref "LQ_KXXP144-SYSVG") (pin "48") (pinfunction "PTA5_48") (pintype "passive"))
    )
    (net (code "98") (name "unconnected-(LQ_KXXP144-SYSVG-PTA6-Pad49)") (class "Default")
      (node (ref "LQ_KXXP144-SYSVG") (pin "49") (pinfunction "PTA6_49") (pintype "passive"))
    )
    (net (code "99") (name "unconnected-(LQ_KXXP144-SYSVG-PTA7-Pad50)") (class "Default")
      (node (ref "LQ_KXXP144-SYSVG") (pin "50") (pinfunction "PTA7_50") (pintype "passive"))
    )
    (net (code "100") (name "unconnected-(LQ_KXXP144-SYSVG-PTA9-Pad52)") (class "Default")
      (node (ref "LQ_KXXP144-SYSVG") (pin "52") (pinfunction "PTA9_52") (pintype "passive"))
    )
    (net (code "101") (name "unconnected-(LQ_KXXP144-SYSVG-PTA10-Pad53)") (class "Default")
      (node (ref "LQ_KXXP144-SYSVG") (pin "53") (pinfunction "PTA10_53") (pintype "passive"))
    )
    (net (code "102") (name "unconnected-(LQ_KXXP144-SYSVG-PTA11-Pad54)") (class "Default")
      (node (ref "LQ_KXXP144-SYSVG") (pin "54") (pinfunction "PTA11_54") (pintype "passive"))
    )
    (net (code "103") (name "unconnected-(LQ_KXXP144-SYSVG-PTA14-Pad57)") (class "Default")
      (node (ref "LQ_KXXP144-SYSVG") (pin "57") (pinfunction "PTA14_57") (pintype "passive"))
    )
    (net (code "104") (name "unconnected-(LQ_KXXP144-SYSVG-PTA15-Pad58)") (class "Default")
      (node (ref "LQ_KXXP144-SYSVG") (pin "58") (pinfunction "PTA15_58") (pintype "passive"))
    )
    (net (code "105") (name "unconnected-(LQ_KXXP144-SYSVG-PTA17-Pad60)") (class "Default")
      (node (ref "LQ_KXXP144-SYSVG") (pin "60") (pinfunction "PTA17_60") (pintype "passive"))
    )
    (net (code "106") (name "unconnected-(LQ_KXXP144-SYSVG-PTA18-Pad61)") (class "Default")
      (node (ref "LQ_KXXP144-SYSVG") (pin "61") (pinfunction "PTA18_61") (pintype "passive"))
    )
    (net (code "107") (name "unconnected-(LQ_KXXP144-SYSVG-PTA24-Pad64)") (class "Default")
      (node (ref "LQ_KXXP144-SYSVG") (pin "64") (pinfunction "PTA24_64") (pintype "passive"))
    )
    (net (code "108") (name "unconnected-(LQ_KXXP144-SYSVG-PTA25-Pad63)") (class "Default")
      (node (ref "LQ_KXXP144-SYSVG") (pin "63") (pinfunction "PTA25_63") (pintype "passive"))
    )
    (net (code "109") (name "unconnected-(LQ_KXXP144-SYSVG-PTA26-Pad66)") (class "Default")
      (node (ref "LQ_KXXP144-SYSVG") (pin "66") (pinfunction "PTA26_66") (pintype "passive"))
    )
    (net (code "110") (name "unconnected-(LQ_KXXP144-SYSVG-PTA27-Pad65)") (class "Default")
      (node (ref "LQ_KXXP144-SYSVG") (pin "65") (pinfunction "PTA27_65") (pintype "passive"))
    )
    (net (code "111") (name "unconnected-(LQ_KXXP144-SYSVG-PTA28-Pad68)") (class "Default")
      (node (ref "LQ_KXXP144-SYSVG") (pin "68") (pinfunction "PTA28_68") (pintype "passive"))
    )
    (net (code "112") (name "unconnected-(LQ_KXXP144-SYSVG-PTA29-Pad67)") (class "Default")
      (node (ref "LQ_KXXP144-SYSVG") (pin "67") (pinfunction "PTA29_67") (pintype "passive"))
    )
    (net (code "113") (name "unconnected-(LQ_KXXP144-SYSVG-PTB4-Pad74)") (class "Default")
      (node (ref "LQ_KXXP144-SYSVG") (pin "74") (pinfunction "PTB4_74") (pintype "passive"))
    )
    (net (code "114") (name "unconnected-(LQ_KXXP144-SYSVG-PTB5-Pad73)") (class "Default")
      (node (ref "LQ_KXXP144-SYSVG") (pin "73") (pinfunction "PTB5_73") (pintype "passive"))
    )
    (net (code "115") (name "unconnected-(LQ_KXXP144-SYSVG-PTB6-Pad76)") (class "Default")
      (node (ref "LQ_KXXP144-SYSVG") (pin "76") (pinfunction "PTB6_76") (pintype "passive"))
    )
    (net (code "116") (name "unconnected-(LQ_KXXP144-SYSVG-PTB7-Pad75)") (class "Default")
      (node (ref "LQ_KXXP144-SYSVG") (pin "75") (pinfunction "PTB7_75") (pintype "passive"))
    )
    (net (code "117") (name "unconnected-(LQ_KXXP144-SYSVG-PTB8-Pad78)") (class "Default")
      (node (ref "LQ_KXXP144-SYSVG") (pin "78") (pinfunction "PTB8_78") (pintype "passive"))
    )
    (net (code "118") (name "unconnected-(LQ_KXXP144-SYSVG-PTB9-Pad77)") (class "Default")
      (node (ref "LQ_KXXP144-SYSVG") (pin "77") (pinfunction "PTB9_77") (pintype "passive"))
    )
    (net (code "119") (name "unconnected-(LQ_KXXP144-SYSVG-PTB18-Pad84)") (class "Default")
      (node (ref "LQ_KXXP144-SYSVG") (pin "84") (pinfunction "PTB18_84") (pintype "passive"))
    )
    (net (code "120") (name "unconnected-(LQ_KXXP144-SYSVG-PTB23-Pad87)") (class "Default")
      (node (ref "LQ_KXXP144-SYSVG") (pin "87") (pinfunction "PTB23_87") (pintype "passive"))
    )
    (net (code "121") (name "unconnected-(LQ_KXXP144-SYSVG-PTC0-Pad90)") (class "Default")
      (node (ref "LQ_KXXP144-SYSVG") (pin "90") (pinfunction "PTC0_90") (pintype "passive"))
    )
    (net (code "122") (name "unconnected-(LQ_KXXP144-SYSVG-PTC5-Pad93)") (class "Default")
      (node (ref "LQ_KXXP144-SYSVG") (pin "93") (pinfunction "PTC5_93") (pintype "passive"))
    )
    (net (code "123") (name "unconnected-(LQ_KXXP144-SYSVG-PTC12-Pad102)") (class "Default")
      (node (ref "LQ_KXXP144-SYSVG") (pin "102") (pinfunction "PTC12_102") (pintype "passive"))
    )
    (net (code "124") (name "unconnected-(LQ_KXXP144-SYSVG-PTC17-Pad105)") (class "Default")
      (node (ref "LQ_KXXP144-SYSVG") (pin "105") (pinfunction "PTC17_105") (pintype "passive"))
    )
    (net (code "125") (name "unconnected-(LQ_KXXP144-SYSVG-PTD8-Pad118)") (class "Default")
      (node (ref "LQ_KXXP144-SYSVG") (pin "118") (pinfunction "PTD8_118") (pintype "passive"))
    )
    (net (code "126") (name "unconnected-(LQ_KXXP144-SYSVG-PTD9-Pad117)") (class "Default")
      (node (ref "LQ_KXXP144-SYSVG") (pin "117") (pinfunction "PTD9_117") (pintype "passive"))
    )
    (net (code "127") (name "unconnected-(LQ_KXXP144-SYSVG-PTD10-Pad120)") (class "Default")
      (node (ref "LQ_KXXP144-SYSVG") (pin "120") (pinfunction "PTD10_120") (pintype "passive"))
    )
    (net (code "128") (name "unconnected-(LQ_KXXP144-SYSVG-PTD11-Pad119)") (class "Default")
      (node (ref "LQ_KXXP144-SYSVG") (pin "119") (pinfunction "PTD11_119") (pintype "passive"))
    )
    (net (code "129") (name "unconnected-(LQ_KXXP144-SYSVG-PTD12-Pad122)") (class "Default")
      (node (ref "LQ_KXXP144-SYSVG") (pin "122") (pinfunction "PTD12_122") (pintype "passive"))
    )
    (net (code "130") (name "unconnected-(LQ_KXXP144-SYSVG-PTD13-Pad121)") (class "Default")
      (node (ref "LQ_KXXP144-SYSVG") (pin "121") (pinfunction "PTD13_121") (pintype "passive"))
    )
    (net (code "131") (name "unconnected-(LQ_KXXP144-SYSVG-PTD14-Pad124)") (class "Default")
      (node (ref "LQ_KXXP144-SYSVG") (pin "124") (pinfunction "PTD14_124") (pintype "passive"))
    )
    (net (code "132") (name "unconnected-(LQ_KXXP144-SYSVG-PTD15-Pad123)") (class "Default")
      (node (ref "LQ_KXXP144-SYSVG") (pin "123") (pinfunction "PTD15_123") (pintype "passive"))
    )
    (net (code "133") (name "unconnected-(LQ_KXXP144-SYSVG-PTE6-Pad7)") (class "Default")
      (node (ref "LQ_KXXP144-SYSVG") (pin "7") (pinfunction "PTE6_7") (pintype "passive"))
    )
    (net (code "134") (name "unconnected-(LQ_KXXP144-SYSVG-PTE26-Pad34)") (class "Default")
      (node (ref "LQ_KXXP144-SYSVG") (pin "34") (pinfunction "PTE26_34") (pintype "passive"))
    )
    (net (code "135") (name "unconnected-(LQ_KXXP144-SYSVG-PTE27-Pad35)") (class "Default")
      (node (ref "LQ_KXXP144-SYSVG") (pin "35") (pinfunction "PTE27_35") (pintype "passive"))
    )
    (net (code "136") (name "unconnected-(LQ_KXXP144-SYSVG-PTE28-Pad36)") (class "Default")
      (node (ref "LQ_KXXP144-SYSVG") (pin "36") (pinfunction "PTE28_36") (pintype "passive"))
    )
    (net (code "137") (name "unconnected-(LQ_KXXP144-SYSVG-RESET-Pad38)") (class "Default")
      (node (ref "LQ_KXXP144-SYSVG") (pin "38") (pinfunction "RESET_38") (pintype "passive"))
    )
    (net (code "138") (name "unconnected-(LQ_KXXP144-SYSVG-USB0_DM-Pad15)") (class "Default")
      (node (ref "LQ_KXXP144-SYSVG") (pin "15") (pinfunction "USB0_DM_15") (pintype "passive"))
    )
    (net (code "139") (name "unconnected-(LQ_KXXP144-SYSVG-USB0_DP-Pad14)") (class "Default")
      (node (ref "LQ_KXXP144-SYSVG") (pin "14") (pinfunction "USB0_DP_14") (pintype "passive"))
    )
    (net (code "140") (name "unconnected-(LQ_KXXP144-SYSVG-VREFH-Pad25)") (class "Default")
      (node (ref "LQ_KXXP144-SYSVG") (pin "25") (pinfunction "VREFH_25") (pintype "passive"))
    )
    (net (code "141") (name "unconnected-(LQ_KXXP144-SYSVG-VREGIN-Pad16)") (class "Default")
      (node (ref "LQ_KXXP144-SYSVG") (pin "16") (pinfunction "VREGIN_16") (pintype "passive"))
    )
    (net (code "142") (name "unconnected-(OLED-Pad7)") (class "Default")
      (node (ref "OLED") (pin "7") (pinfunction "7_7") (pintype "passive+no_connect"))
    )
    (net (code "143") (name "unconnected-(RP1-Pad3)") (class "Default")
      (node (ref "RP1") (pin "3") (pinfunction "3_3") (pintype "passive"))
    )
    (net (code "144") (name "unconnected-(RP1-Pad4)") (class "Default")
      (node (ref "RP1") (pin "4") (pinfunction "4_4") (pintype "passive"))
    )
    (net (code "145") (name "unconnected-(RP2-Pad5)") (class "Default")
      (node (ref "RP2") (pin "5") (pinfunction "5_5") (pintype "passive"))
    )
    (net (code "146") (name "unconnected-(SW-Pad3)") (class "Default")
      (node (ref "SW") (pin "3") (pinfunction "3_3") (pintype "passive+no_connect"))
    )
    (net (code "147") (name "unconnected-(VR-A-Pad1)") (class "Default")
      (node (ref "VR") (pin "1") (pinfunction "A_1") (pintype "passive"))
    )
  )
)
